# Sheet1.net
KiCad netlist of a schematic drawn in Altium Designer
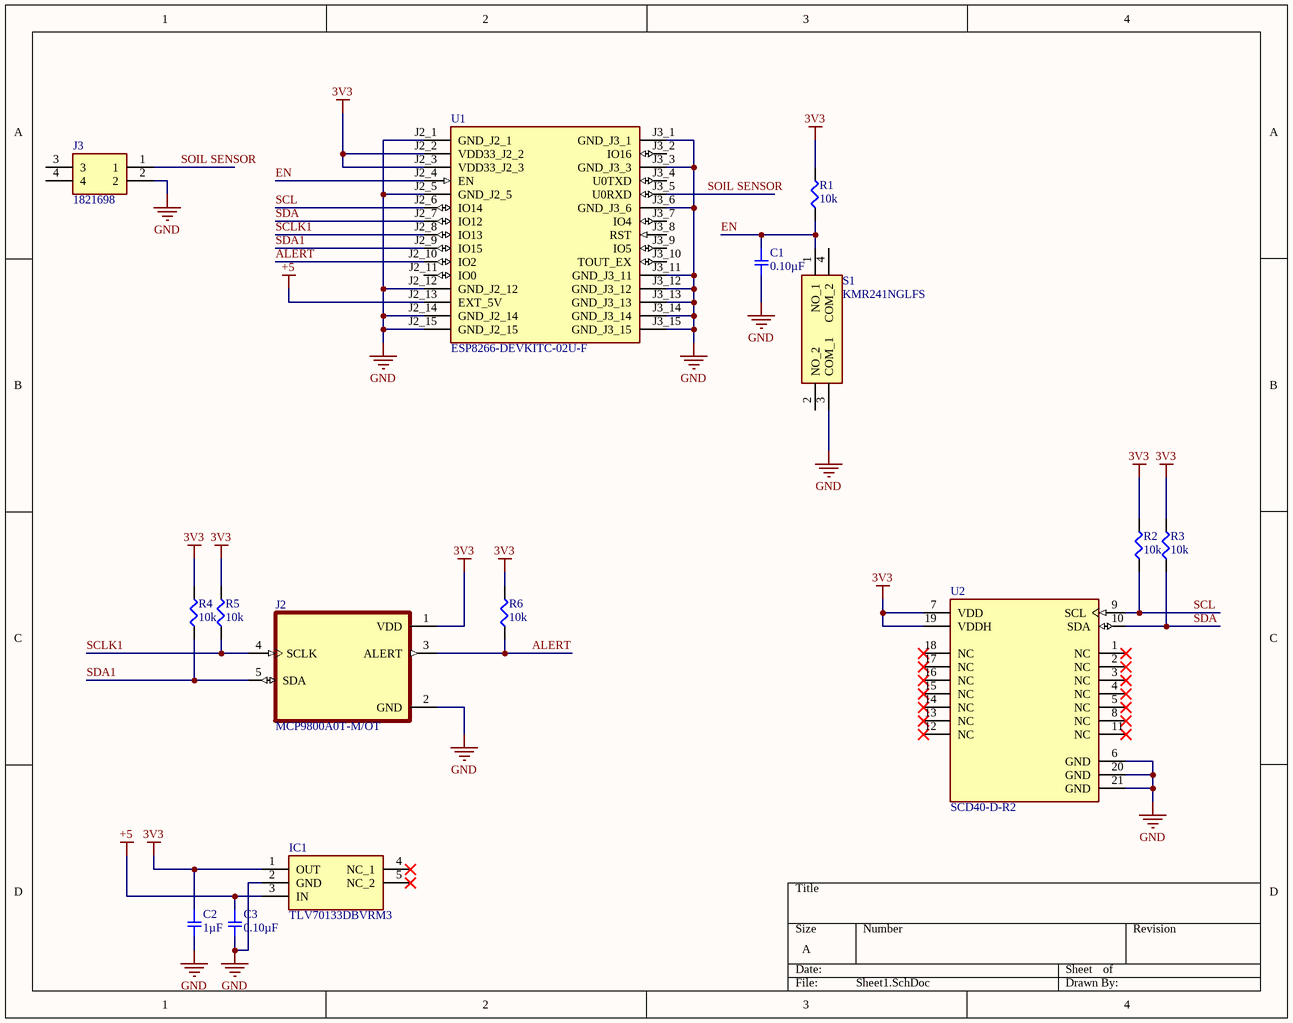
[diagram p0: Sheet1.SchDoc]

(export (version "E")
  (design (tool "Eeschema 10.0.6"))
  (components
    (comp (ref "C1")
      (value "0.10µF")
      (footprint "SMD-0402C")
      (description "CAP CER 0.1UF 16V X7R 0402")
      (fields
        (field (name "DIGI-KEY PART NUMBER") "490-4759-1-ND")
        (field (name "PART NUMBER") "GCM155R71C104KA55D")
      )
      (libsource (lib "capacitor_murata_0402") (part "GCM155R71C104KA55D"))
    )
    (comp (ref "C2")
      (value "1µF")
      (footprint "SMD-0402C")
      (description "CAP CER 1UF 16V X6S 0402")
      (fields
        (field (name "DIGI-KEY PART NUMBER") "490-12700-1-ND")
        (field (name "PART NUMBER") "GRM155C81C105KE11D")
      )
      (libsource (lib "capacitor_murata_0402") (part "GRM155C81C105KE11D"))
    )
    (comp (ref "C3")
      (value "0.10µF")
      (footprint "SMD-0402C")
      (description "CAP CER 0.1UF 16V X7R 0402")
      (fields
        (field (name "DIGI-KEY PART NUMBER") "490-4759-1-ND")
        (field (name "PART NUMBER") "GCM155R71C104KA55D")
      )
      (libsource (lib "capacitor_murata_0402") (part "GCM155R71C104KA55D"))
    )
    (comp (ref "IC1")
      (value "TLV70133DBVRM3")
      (footprint "SamacSys:SOT95P280X145-5N")
      (description "Integrated Circuit")
      (fields (field (name "MOUSER PART NUMBER") "595-TLV70133DBVRM3"))
      (libsource (lib "*") (part "TLV70133DBVRM3"))
    )
    (comp (ref "J2")
      (value "MCP9800A0T-M/OT")
      (footprint "MCP9800A0T-M_OT:SOT95P270X145-5N")
      (fields (field (name "MF") "{'manufacturer': u'Microchip Technology'}"))
      (libsource (lib "*") (part "MCP9800A0T-M/OT"))
    )
    (comp (ref "J3")
      (value "1821698")
      (footprint "SamacSys:1821698")
      (description "Connector")
      (fields (field (name "MOUSER PART NUMBER") "651-1821698"))
      (libsource (lib "SamacSys") (part "1821698"))
    )
    (comp (ref "R1")
      (value "10k")
      (footprint "SMD-0402-RES")
      (description "RES SMD 10K OHM 5% 1/10W 0402")
      (fields (field (name "PART NUMBER") "ERJ-2GEJ103X") (field (name "DIGI-KEY PART NUMBER") "P10KJCT-ND"))
      (libsource (lib "Panasonic_ERJ_0402") (part "ERJ-2GEJ103X"))
    )
    (comp (ref "R2")
      (value "10k")
      (footprint "SMD-0402-RES")
      (description "RES SMD 10K OHM 5% 1/10W 0402")
      (fields (field (name "PART NUMBER") "ERJ-2GEJ103X") (field (name "DIGI-KEY PART NUMBER") "P10KJCT-ND"))
      (libsource (lib "Panasonic_ERJ_0402") (part "ERJ-2GEJ103X"))
    )
    (comp (ref "R3")
      (value "10k")
      (footprint "SMD-0402-RES")
      (description "RES SMD 10K OHM 5% 1/10W 0402")
      (fields (field (name "PART NUMBER") "ERJ-2GEJ103X") (field (name "DIGI-KEY PART NUMBER") "P10KJCT-ND"))
      (libsource (lib "Panasonic_ERJ_0402") (part "ERJ-2GEJ103X"))
    )
    (comp (ref "R4")
      (value "10k")
      (footprint "SMD-0402-RES")
      (description "RES SMD 10K OHM 5% 1/10W 0402")
      (fields (field (name "PART NUMBER") "ERJ-2GEJ103X") (field (name "DIGI-KEY PART NUMBER") "P10KJCT-ND"))
      (libsource (lib "Panasonic_ERJ_0402") (part "ERJ-2GEJ103X"))
    )
    (comp (ref "R5")
      (value "10k")
      (footprint "SMD-0402-RES")
      (description "RES SMD 10K OHM 5% 1/10W 0402")
      (fields (field (name "PART NUMBER") "ERJ-2GEJ103X") (field (name "DIGI-KEY PART NUMBER") "P10KJCT-ND"))
      (libsource (lib "Panasonic_ERJ_0402") (part "ERJ-2GEJ103X"))
    )
    (comp (ref "R6")
      (value "10k")
      (footprint "SMD-0402-RES")
      (description "RES SMD 10K OHM 5% 1/10W 0402")
      (fields (field (name "PART NUMBER") "ERJ-2GEJ103X") (field (name "DIGI-KEY PART NUMBER") "P10KJCT-ND"))
      (libsource (lib "Panasonic_ERJ_0402") (part "ERJ-2GEJ103X"))
    )
    (comp (ref "S1")
      (value "KMR241NGLFS")
      (footprint "SamacSys:KMR241NGLFS")
      (description "Switch")
      (fields (field (name "MOUSER PART NUMBER") "611-KMR241NGLFS"))
      (libsource (lib "SamacSys") (part "KMR241NGLFS"))
    )
    (comp (ref "U1")
      (value "ESP8266-DEVKITC-02U-F")
      (footprint "ESP8266-DEVKITC-02U-F:MODULE_ESP8266-DEVKITC-02U-F")
      (fields (field (name "MF") "{'manufacturer': u'Espressif Systems'}"))
      (libsource (lib "*") (part "ESP8266-DEVKITC-02U-F"))
    )
    (comp (ref "U2")
      (value "SCD40-D-R2")
      (footprint "FP-SCD40-D-R2-MFG")
      (description "CO2 SENSOR 50 PPM I2C SMD")
      (libsource (lib "Altium Content Vault") (part "860b1291be8b6ca23305e01f328347a"))
    )
  )
  (nets
    (net (code "1") (name "+5") (class "Default")
      (node (ref "C3") (pin "1") (pinfunction "1_1") (pintype "passive"))
      (node (ref "IC1") (pin "3") (pinfunction "IN_3") (pintype "passive"))
      (node (ref "U1") (pin "J2_13") (pinfunction "EXT_5V_J2_13") (pintype "power_in"))
    )
    (net (code "2") (name "/ALERT") (class "Default")
      (node (ref "J2") (pin "3") (pinfunction "ALERT_3") (pintype "output"))
      (node (ref "R6") (pin "1") (pinfunction "1_1") (pintype "passive"))
      (node (ref "U1") (pin "J2_10") (pinfunction "IO2_J2_10") (pintype "bidirectional"))
    )
    (net (code "3") (name "/EN") (class "Default")
      (node (ref "C1") (pin "1") (pinfunction "1_1") (pintype "passive"))
      (node (ref "R1") (pin "1") (pinfunction "1_1") (pintype "passive"))
      (node (ref "S1") (pin "1") (pinfunction "NO_1_1") (pintype "passive"))
      (node (ref "U1") (pin "J2_4") (pinfunction "EN_J2_4") (pintype "input"))
    )
    (net (code "4") (name "/SCL") (class "Default")
      (node (ref "R2") (pin "1") (pinfunction "1_1") (pintype "passive"))
      (node (ref "U1") (pin "J2_6") (pinfunction "IO14_J2_6") (pintype "bidirectional"))
      (node (ref "U2") (pin "9") (pinfunction "SCL_9") (pintype "input"))
    )
    (net (code "5") (name "/SCLK1") (class "Default")
      (node (ref "J2") (pin "4") (pinfunction "SCLK_4") (pintype "input"))
      (node (ref "R5") (pin "1") (pinfunction "1_1") (pintype "passive"))
      (node (ref "U1") (pin "J2_8") (pinfunction "IO13_J2_8") (pintype "bidirectional"))
    )
    (net (code "6") (name "/SDA") (class "Default")
      (node (ref "R3") (pin "1") (pinfunction "1_1") (pintype "passive"))
      (node (ref "U1") (pin "J2_7") (pinfunction "IO12_J2_7") (pintype "bidirectional"))
      (node (ref "U2") (pin "10") (pinfunction "SDA_10") (pintype "bidirectional"))
    )
    (net (code "7") (name "/SDA1") (class "Default")
      (node (ref "J2") (pin "5") (pinfunction "SDA_5") (pintype "bidirectional"))
      (node (ref "R4") (pin "1") (pinfunction "1_1") (pintype "passive"))
      (node (ref "U1") (pin "J2_9") (pinfunction "IO15_J2_9") (pintype "bidirectional"))
    )
    (net (code "8") (name "/SOIL SENSOR") (class "Default")
      (node (ref "J3") (pin "1") (pinfunction "1_1") (pintype "passive"))
      (node (ref "U1") (pin "J3_5") (pinfunction "U0RXD_J3_5") (pintype "bidirectional"))
    )
    (net (code "9") (name "3V3") (class "Default")
      (node (ref "C2") (pin "1") (pinfunction "1_1") (pintype "passive"))
      (node (ref "IC1") (pin "1") (pinfunction "OUT_1") (pintype "passive"))
      (node (ref "J2") (pin "1") (pinfunction "VDD_1") (pintype "power_in"))
      (node (ref "R1") (pin "2") (pinfunction "2_2") (pintype "passive"))
      (node (ref "R2") (pin "2") (pinfunction "2_2") (pintype "passive"))
      (node (ref "R3") (pin "2") (pinfunction "2_2") (pintype "passive"))
      (node (ref "R4") (pin "2") (pinfunction "2_2") (pintype "passive"))
      (node (ref "R5") (pin "2") (pinfunction "2_2") (pintype "passive"))
      (node (ref "R6") (pin "2") (pinfunction "2_2") (pintype "passive"))
      (node (ref "U1") (pin "J2_2") (pinfunction "VDD33_J2_2_J2_2") (pintype "power_in"))
      (node (ref "U1") (pin "J2_3") (pinfunction "VDD33_J2_3_J2_3") (pintype "power_in"))
      (node (ref "U2") (pin "19") (pinfunction "VDDH_19") (pintype "power_in"))
      (node (ref "U2") (pin "7") (pinfunction "VDD_7") (pintype "power_in"))
    )
    (net (code "10") (name "GND") (class "Default")
      (node (ref "C1") (pin "2") (pinfunction "2_2") (pintype "passive"))
      (node (ref "C2") (pin "2") (pinfunction "2_2") (pintype "passive"))
      (node (ref "C3") (pin "2") (pinfunction "2_2") (pintype "passive"))
      (node (ref "IC1") (pin "2") (pinfunction "GND_2") (pintype "passive"))
      (node (ref "J2") (pin "2") (pinfunction "GND_2") (pintype "power_in"))
      (node (ref "J3") (pin "2") (pinfunction "2_2") (pintype "passive"))
      (node (ref "S1") (pin "3") (pinfunction "COM_1_3") (pintype "passive"))
      (node (ref "U1") (pin "J2_1") (pinfunction "GND_J2_1_J2_1") (pintype "power_in"))
      (node (ref "U1") (pin "J2_12") (pinfunction "GND_J2_12_J2_12") (pintype "power_in"))
      (node (ref "U1") (pin "J2_14") (pinfunction "GND_J2_14_J2_14") (pintype "power_in"))
      (node (ref "U1") (pin "J2_15") (pinfunction "GND_J2_15_J2_15") (pintype "power_in"))
      (node (ref "U1") (pin "J2_5") (pinfunction "GND_J2_5_J2_5") (pintype "power_in"))
      (node (ref "U1") (pin "J3_1") (pinfunction "GND_J3_1_J3_1") (pintype "power_in"))
      (node (ref "U1") (pin "J3_11") (pinfunction "GND_J3_11_J3_11") (pintype "power_in"))
      (node (ref "U1") (pin "J3_12") (pinfunction "GND_J3_12_J3_12") (pintype "power_in"))
      (node (ref "U1") (pin "J3_13") (pinfunction "GND_J3_13_J3_13") (pintype "power_in"))
      (node (ref "U1") (pin "J3_14") (pinfunction "GND_J3_14_J3_14") (pintype "power_in"))
      (node (ref "U1") (pin "J3_15") (pinfunction "GND_J3_15_J3_15") (pintype "power_in"))
      (node (ref "U1") (pin "J3_3") (pinfunction "GND_J3_3_J3_3") (pintype "power_in"))
      (node (ref "U1") (pin "J3_6") (pinfunction "GND_J3_6_J3_6") (pintype "power_in"))
      (node (ref "U2") (pin "20") (pinfunction "GND_20") (pintype "power_in"))
      (node (ref "U2") (pin "21") (pinfunction "GND_21") (pintype "power_in"))
      (node (ref "U2") (pin "6") (pinfunction "GND_6") (pintype "power_in"))
    )
    (net (code "11") (name "unconnected-(IC1-NC_1-Pad4)") (class "Default")
      (node (ref "IC1") (pin "4") (pinfunction "NC_1_4") (pintype "passive+no_connect"))
    )
    (net (code "12") (name "unconnected-(IC1-NC_2-Pad5)") (class "Default")
      (node (ref "IC1") (pin "5") (pinfunction "NC_2_5") (pintype "passive+no_connect"))
    )
    (net (code "13") (name "unconnected-(J3-Pad3)") (class "Default")
      (node (ref "J3") (pin "3") (pinfunction "3_3") (pintype "passive"))
    )
    (net (code "14") (name "unconnected-(J3-Pad4)") (class "Default")
      (node (ref "J3") (pin "4") (pinfunction "4_4") (pintype "passive"))
    )
    (net (code "15") (name "unconnected-(S1-COM_2-Pad4)") (class "Default")
      (node (ref "S1") (pin "4") (pinfunction "COM_2_4") (pintype "passive"))
    )
    (net (code "16") (name "unconnected-(S1-NO_2-Pad2)") (class "Default")
      (node (ref "S1") (pin "2") (pinfunction "NO_2_2") (pintype "passive"))
    )
    (net (code "17") (name "unconnected-(U1-IO0-PadJ2_11)") (class "Default")
      (node (ref "U1") (pin "J2_11") (pinfunction "IO0_J2_11") (pintype "bidirectional"))
    )
    (net (code "18") (name "unconnected-(U1-IO4-PadJ3_7)") (class "Default")
      (node (ref "U1") (pin "J3_7") (pinfunction "IO4_J3_7") (pintype "bidirectional"))
    )
    (net (code "19") (name "unconnected-(U1-IO5-PadJ3_9)") (class "Default")
      (node (ref "U1") (pin "J3_9") (pinfunction "IO5_J3_9") (pintype "bidirectional"))
    )
    (net (code "20") (name "unconnected-(U1-IO16-PadJ3_2)") (class "Default")
      (node (ref "U1") (pin "J3_2") (pinfunction "IO16_J3_2") (pintype "bidirectional"))
    )
    (net (code "21") (name "unconnected-(U1-RST-PadJ3_8)") (class "Default")
      (node (ref "U1") (pin "J3_8") (pinfunction "RST_J3_8") (pintype "input"))
    )
    (net (code "22") (name "unconnected-(U1-TOUT_EX-PadJ3_10)") (class "Default")
      (node (ref "U1") (pin "J3_10") (pinfunction "TOUT_EX_J3_10") (pintype "bidirectional"))
    )
    (net (code "23") (name "unconnected-(U1-U0TXD-PadJ3_4)") (class "Default")
      (node (ref "U1") (pin "J3_4") (pinfunction "U0TXD_J3_4") (pintype "bidirectional"))
    )
    (net (code "24") (name "unconnected-(U2-NC-Pad1)") (class "Default")
      (node (ref "U2") (pin "1") (pinfunction "NC_1") (pintype "passive+no_connect"))
    )
    (net (code "25") (name "unconnected-(U2-NC-Pad2)") (class "Default")
      (node (ref "U2") (pin "2") (pinfunction "NC_2") (pintype "passive+no_connect"))
    )
    (net (code "26") (name "unconnected-(U2-NC-Pad3)") (class "Default")
      (node (ref "U2") (pin "3") (pinfunction "NC_3") (pintype "passive+no_connect"))
    )
    (net (code "27") (name "unconnected-(U2-NC-Pad4)") (class "Default")
      (node (ref "U2") (pin "4") (pinfunction "NC_4") (pintype "passive+no_connect"))
    )
    (net (code "28") (name "unconnected-(U2-NC-Pad5)") (class "Default")
      (node (ref "U2") (pin "5") (pinfunction "NC_5") (pintype "passive+no_connect"))
    )
    (net (code "29") (name "unconnected-(U2-NC-Pad8)") (class "Default")
      (node (ref "U2") (pin "8") (pinfunction "NC_8") (pintype "passive+no_connect"))
    )
    (net (code "30") (name "unconnected-(U2-NC-Pad11)") (class "Default")
      (node (ref "U2") (pin "11") (pinfunction "NC_11") (pintype "passive+no_connect"))
    )
    (net (code "31") (name "unconnected-(U2-NC-Pad12)") (class "Default")
      (node (ref "U2") (pin "12") (pinfunction "NC_12") (pintype "passive+no_connect"))
    )
    (net (code "32") (name "unconnected-(U2-NC-Pad13)") (class "Default")
      (node (ref "U2") (pin "13") (pinfunction "NC_13") (pintype "passive+no_connect"))
    )
    (net (code "33") (name "unconnected-(U2-NC-Pad14)") (class "Default")
      (node (ref "U2") (pin "14") (pinfunction "NC_14") (pintype "passive+no_connect"))
    )
    (net (code "34") (name "unconnected-(U2-NC-Pad15)") (class "Default")
      (node (ref "U2") (pin "15") (pinfunction "NC_15") (pintype "passive+no_connect"))
    )
    (net (code "35") (name "unconnected-(U2-NC-Pad16)") (class "Default")
      (node (ref "U2") (pin "16") (pinfunction "NC_16") (pintype "passive+no_connect"))
    )
    (net (code "36") (name "unconnected-(U2-NC-Pad17)") (class "Default")
      (node (ref "U2") (pin "17") (pinfunction "NC_17") (pintype "passive+no_connect"))
    )
    (net (code "37") (name "unconnected-(U2-NC-Pad18)") (class "Default")
      (node (ref "U2") (pin "18") (pinfunction "NC_18") (pintype "passive+no_connect"))
    )
  )
)
